# ProDoc_DRV8701_2_2025-04-30.net
KiCad netlist of a schematic drawn in EasyEDA Pro
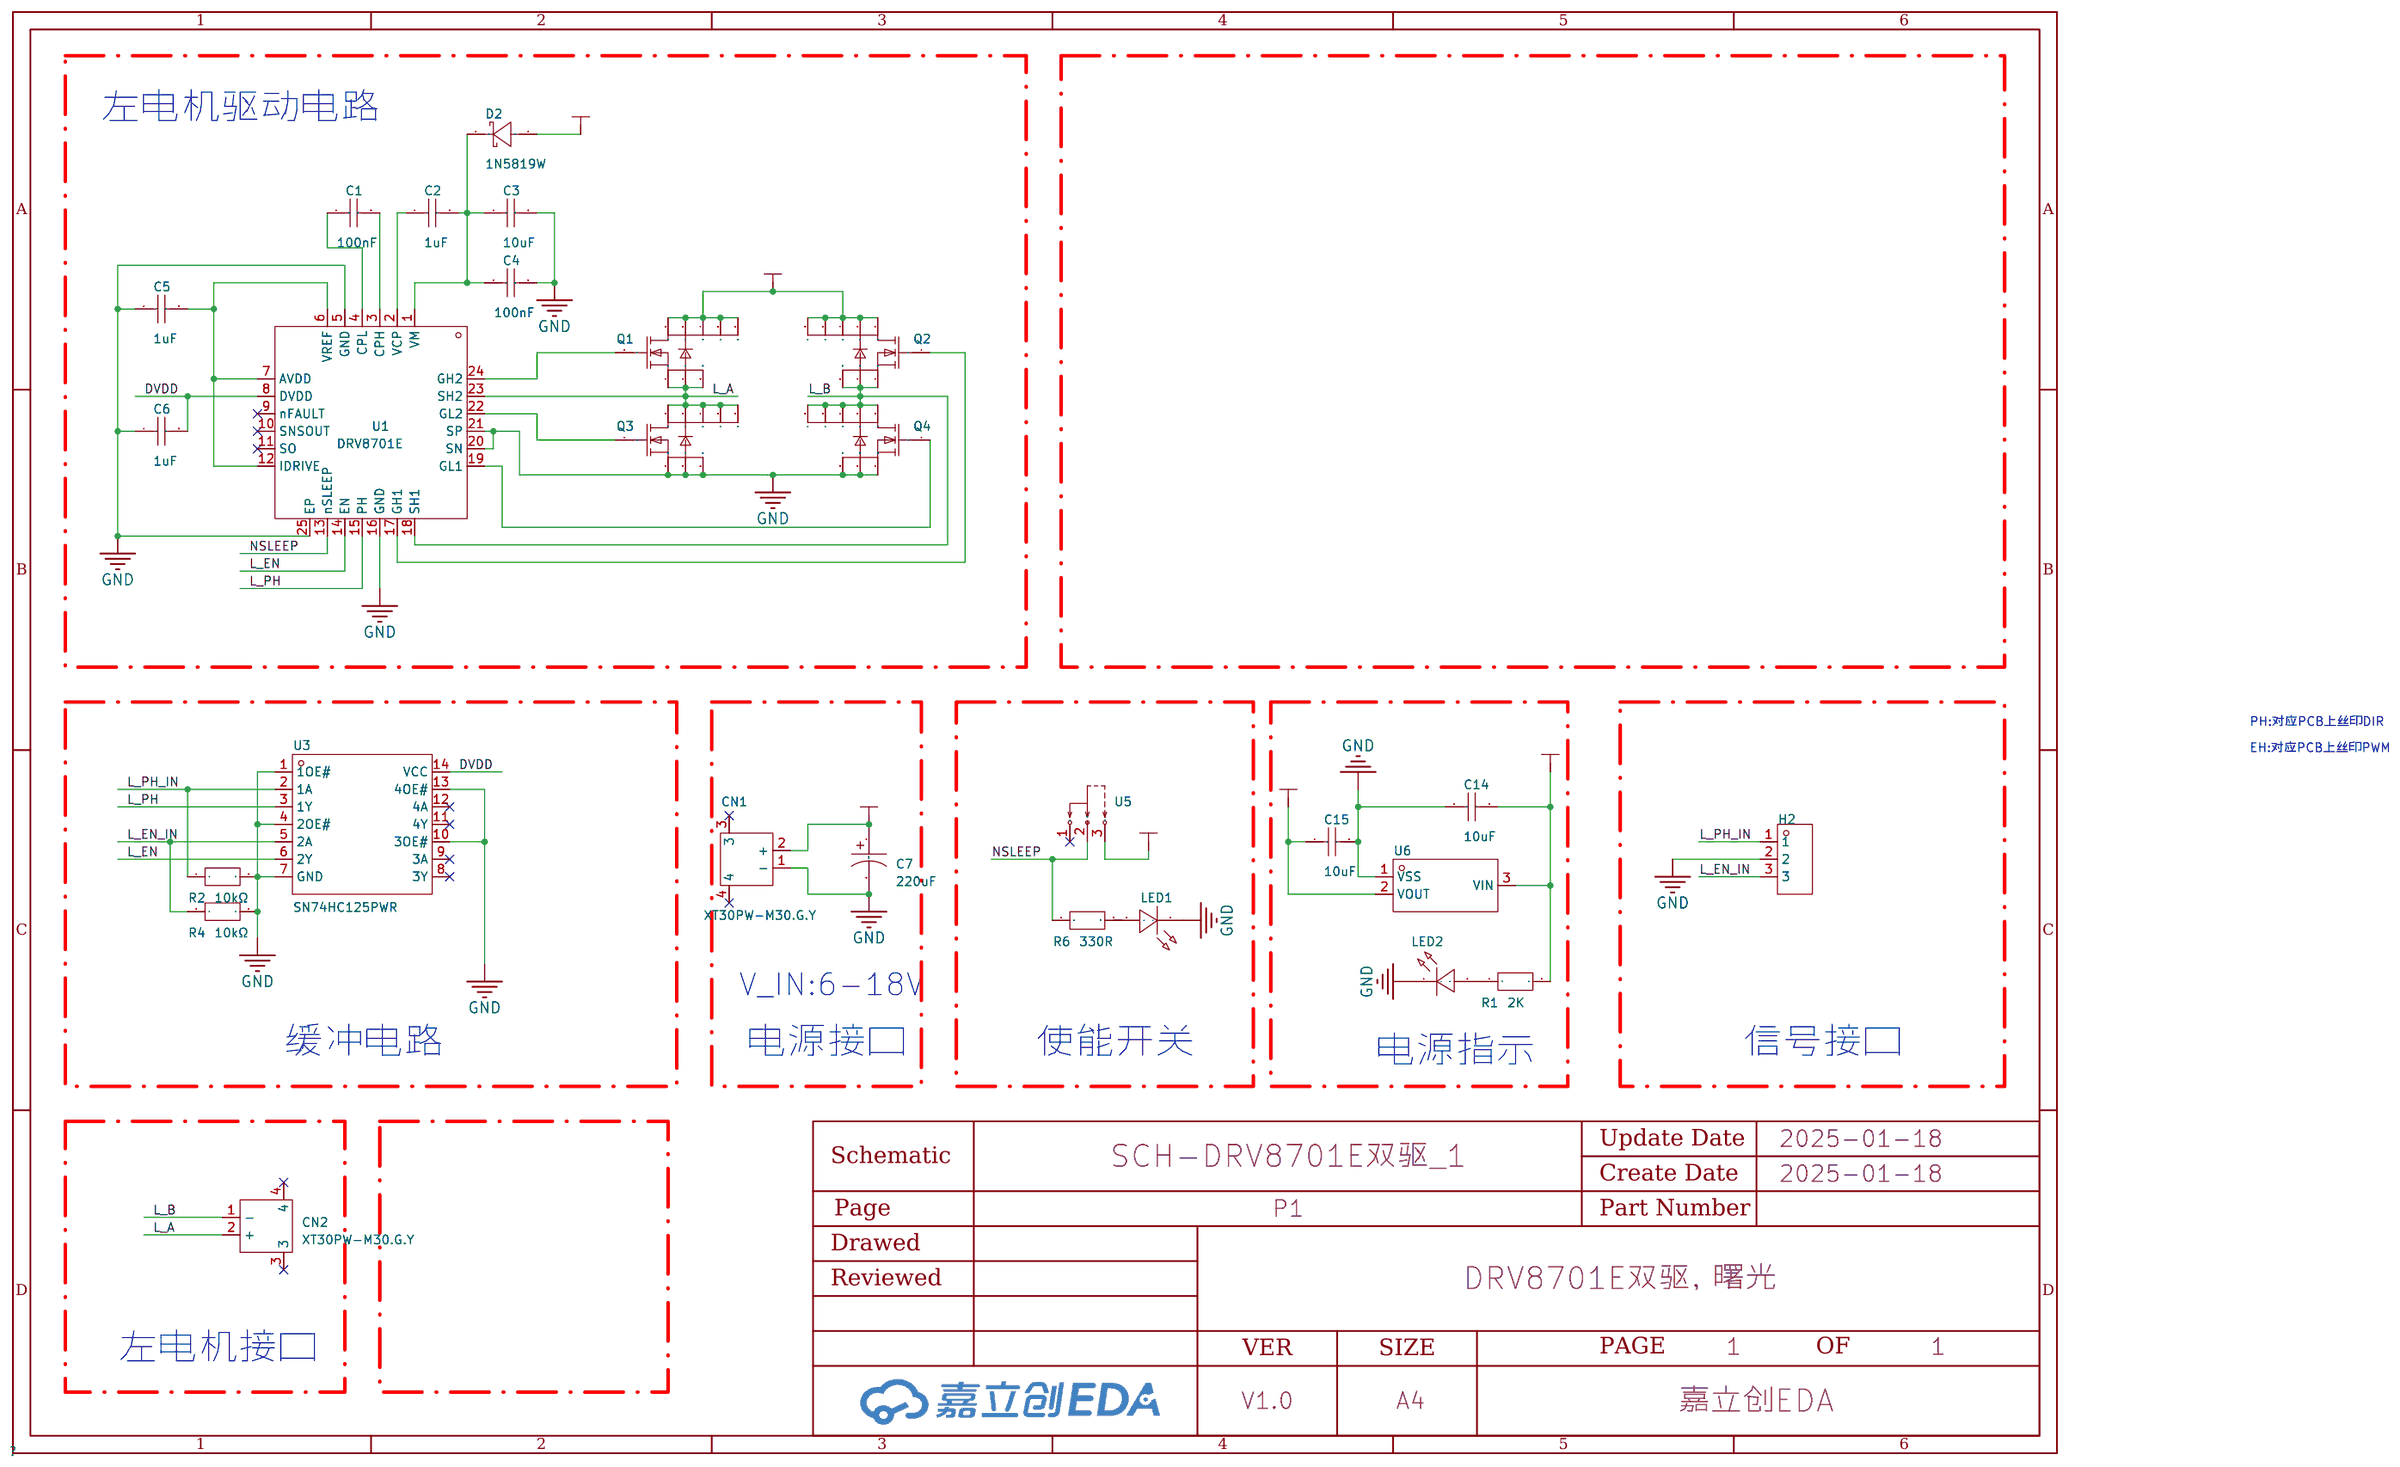
[diagram p0: schematic sheet]

(export (version "E")
  (design (tool "Eeschema 10.0.6"))
  (components
    (comp (ref "C1")
      (value "100nF")
      (footprint "easyedapro:C0805")
      (description "容值:100nF;精度:±10%;额定电压:50V;材质(温度系数):X7R;")
      (fields
        (field (name "Manufacturer Part") "CL21B104KBCNNNC")
        (field (name "Manufacturer") "SAMSUNG(三星)")
      )
      (libsource (lib "easyedapro") (part "CL21B104KBCNNNC"))
    )
    (comp (ref "C2")
      (value "1uF")
      (footprint "easyedapro:C0805")
      (description "容值:100nF;精度:±10%;额定电压:50V;材质(温度系数):X7R;")
      (fields
        (field (name "Manufacturer Part") "CL21B104KBCNNNC")
        (field (name "Manufacturer") "SAMSUNG(三星)")
      )
      (libsource (lib "easyedapro") (part "CL21B104KBCNNNC"))
    )
    (comp (ref "C3")
      (value "10uF")
      (footprint "easyedapro:C0805")
      (description "容值:100nF;精度:±10%;额定电压:50V;材质(温度系数):X7R;")
      (fields
        (field (name "Manufacturer Part") "CL21B104KBCNNNC")
        (field (name "Manufacturer") "SAMSUNG(三星)")
      )
      (libsource (lib "easyedapro") (part "CL21B104KBCNNNC"))
    )
    (comp (ref "C4")
      (value "100nF")
      (footprint "easyedapro:C0805")
      (description "容值:100nF;精度:±10%;额定电压:50V;材质(温度系数):X7R;")
      (fields
        (field (name "Manufacturer Part") "CL21B104KBCNNNC")
        (field (name "Manufacturer") "SAMSUNG(三星)")
      )
      (libsource (lib "easyedapro") (part "CL21B104KBCNNNC"))
    )
    (comp (ref "C5")
      (value "1uF")
      (footprint "easyedapro:C0805")
      (description "容值:100nF;精度:±10%;额定电压:50V;材质(温度系数):X7R;")
      (fields
        (field (name "Manufacturer Part") "CL21B104KBCNNNC")
        (field (name "Manufacturer") "SAMSUNG(三星)")
      )
      (libsource (lib "easyedapro") (part "CL21B104KBCNNNC"))
    )
    (comp (ref "C6")
      (value "1uF")
      (footprint "easyedapro:C0805")
      (description "容值:100nF;精度:±10%;额定电压:50V;材质(温度系数):X7R;")
      (fields
        (field (name "Manufacturer Part") "CL21B104KBCNNNC")
        (field (name "Manufacturer") "SAMSUNG(三星)")
      )
      (libsource (lib "easyedapro") (part "CL21B104KBCNNNC"))
    )
    (comp (ref "C7")
      (value "220uF")
      (footprint "easyedapro:CAP-TH_BD8.0-P3.50-D0.6-FD")
      (fields (field (name "Manufacturer Part") "25PZE220M8X9") (field (name "Manufacturer") "rubycon(红宝石)"))
      (libsource (lib "easyedapro") (part "25PZE220M8X9"))
    )
    (comp (ref "C14")
      (value "10uF")
      (footprint "easyedapro:C0805")
      (description "容值:100nF;精度:±10%;额定电压:50V;材质(温度系数):X7R;")
      (fields
        (field (name "Manufacturer Part") "CL21B104KBCNNNC")
        (field (name "Manufacturer") "SAMSUNG(三星)")
      )
      (libsource (lib "easyedapro") (part "CL21B104KBCNNNC"))
    )
    (comp (ref "C15")
      (value "10uF")
      (footprint "easyedapro:C0805")
      (description "容值:100nF;精度:±10%;额定电压:50V;材质(温度系数):X7R;")
      (fields
        (field (name "Manufacturer Part") "CL21B104KBCNNNC")
        (field (name "Manufacturer") "SAMSUNG(三星)")
      )
      (libsource (lib "easyedapro") (part "CL21B104KBCNNNC"))
    )
    (comp (ref "CN1")
      (value "XT30PW-M30.G.Y")
      (footprint "easyedapro:CONN-TH_XT30PW-M")
      (description "类别:-;类型1:-;")
      (fields (field (name "Manufacturer") "AMASS(艾迈斯)"))
      (libsource (lib "easyedapro") (part "XT30PW-M"))
    )
    (comp (ref "CN2")
      (value "XT30PW-M30.G.Y")
      (footprint "easyedapro:CONN-TH_XT30PW-M")
      (description "类别:-;类型1:-;")
      (fields (field (name "Manufacturer") "AMASS(艾迈斯)"))
      (libsource (lib "easyedapro") (part "XT30PW-M"))
    )
    (comp (ref "D2")
      (value "1N5819W")
      (footprint "easyedapro:SOD-123_L2.7-W1.6-LS3.7-R-RD")
      (description "二极管配置:独立式;直流反向耐压(Vr):40V;平均整流电流(Io):350mA;正向压降(Vf):600mV@200mA;反向电流(Ir):5uA@30V;")
      (fields (field (name "Manufacturer") "JSMSEMI(杰盛微)"))
      (libsource (lib "easyedapro") (part "1N5819W_C963381"))
    )
    (comp (ref "H2")
      (value "~")
      (footprint "easyedapro:HDR-TH_3P-P2.54-V-F")
      (libsource (lib "easyedapro") (part "PM254V-11-03-H85"))
    )
    (comp (ref "LED1")
      (value "P2-0805UVTCS2-0.8T")
      (footprint "easyedapro:LED0805-RD_PURPLE")
      (description "峰值波长:410nm~420nm;发光角度:120°;正向电压:3V;正向电流:30mA;功耗:90mW;工作温度:-40°C~+85°C;抗静电能力:2kV;辐射功率:-;")
      (fields (field (name "Manufacturer") "TUOZHAN(拓展光电)"))
      (libsource (lib "easyedapro") (part "P2-0805UVTCS2-0.8T"))
    )
    (comp (ref "LED2")
      (value "P2-0805UVTCS2-0.8T")
      (footprint "easyedapro:LED0805-RD_PURPLE")
      (description "峰值波长:410nm~420nm;发光角度:120°;正向电压:3V;正向电流:30mA;功耗:90mW;工作温度:-40°C~+85°C;抗静电能力:2kV;辐射功率:-;")
      (fields (field (name "Manufacturer") "TUOZHAN(拓展光电)"))
      (libsource (lib "easyedapro") (part "P2-0805UVTCS2-0.8T"))
    )
    (comp (ref "Q1")
      (value "TPH1R403NL,L1Q(M")
      (footprint "easyedapro:DSOP-8_L5.0-W5.0-P1.27-LS6.0-BL-EP")
      (fields (field (name "Manufacturer") "TOSHIBA(东芝)"))
      (libsource (lib "easyedapro") (part "TPH1R403NL,L1Q(M"))
    )
    (comp (ref "Q2")
      (value "TPH1R403NL,L1Q(M")
      (footprint "easyedapro:DSOP-8_L5.0-W5.0-P1.27-LS6.0-BL-EP")
      (fields (field (name "Manufacturer") "TOSHIBA(东芝)"))
      (libsource (lib "easyedapro") (part "TPH1R403NL,L1Q(M"))
    )
    (comp (ref "Q3")
      (value "TPH1R403NL,L1Q(M")
      (footprint "easyedapro:DSOP-8_L5.0-W5.0-P1.27-LS6.0-BL-EP")
      (fields (field (name "Manufacturer") "TOSHIBA(东芝)"))
      (libsource (lib "easyedapro") (part "TPH1R403NL,L1Q(M"))
    )
    (comp (ref "Q4")
      (value "TPH1R403NL,L1Q(M")
      (footprint "easyedapro:DSOP-8_L5.0-W5.0-P1.27-LS6.0-BL-EP")
      (fields (field (name "Manufacturer") "TOSHIBA(东芝)"))
      (libsource (lib "easyedapro") (part "TPH1R403NL,L1Q(M"))
    )
    (comp (ref "R1")
      (value "2K")
      (footprint "easyedapro:R0805")
      (description "阻值:10kΩ;精度:±5%;功率:500mW;温度系数:±200ppm/°C;最大工作电压:600V;工作温度范围:-55°C~+155°C;")
      (fields (field (name "Manufacturer Part") "ERJP06J103V") (field (name "Manufacturer") "PANASONIC(松下)"))
      (libsource (lib "easyedapro") (part "ERJP06J103V"))
    )
    (comp (ref "R2")
      (value "10kΩ")
      (footprint "easyedapro:R0805")
      (description "阻值:10kΩ;精度:±5%;功率:500mW;温度系数:±200ppm/°C;最大工作电压:600V;工作温度范围:-55°C~+155°C;")
      (fields (field (name "Manufacturer Part") "ERJP06J103V") (field (name "Manufacturer") "PANASONIC(松下)"))
      (libsource (lib "easyedapro") (part "ERJP06J103V"))
    )
    (comp (ref "R4")
      (value "10kΩ")
      (footprint "easyedapro:R0805")
      (description "阻值:10kΩ;精度:±5%;功率:500mW;温度系数:±200ppm/°C;最大工作电压:600V;工作温度范围:-55°C~+155°C;")
      (fields (field (name "Manufacturer Part") "ERJP06J103V") (field (name "Manufacturer") "PANASONIC(松下)"))
      (libsource (lib "easyedapro") (part "ERJP06J103V"))
    )
    (comp (ref "R6")
      (value "330R")
      (footprint "easyedapro:R0805")
      (description "阻值:10kΩ;精度:±5%;功率:500mW;温度系数:±200ppm/°C;最大工作电压:600V;工作温度范围:-55°C~+155°C;")
      (fields (field (name "Manufacturer Part") "ERJP06J103V") (field (name "Manufacturer") "PANASONIC(松下)"))
      (libsource (lib "easyedapro") (part "ERJP06J103V"))
    )
    (comp (ref "U1")
      (value "DRV8701E")
      (footprint "easyedapro:VQFN-24_L4.0-W4.0-P0.50-BL-EP2.5")
      (description "电源电压:0V~5.5V;输出电流:-;接口:并行;")
      (fields (field (name "Manufacturer") "TI(德州仪器)"))
      (libsource (lib "easyedapro") (part "DRV8701ERGET"))
    )
    (comp (ref "U3")
      (value "SN74HC125PWR")
      (footprint "easyedapro:TSSOP-14_L5.0-W4.4-P0.65-LS6.5-BL")
      (description "类型:缓冲器，非反相;电源电压:2V~6V;输入类型:-;输出类型:三态;低电平输出电流(IOL):7.8mA;高电平输出电流(IOH):7.8mA;工作温度:-40°C~+85°C;")
      (fields (field (name "Manufacturer") "TI(德州仪器)"))
      (libsource (lib "easyedapro") (part "SN74HC125PWR"))
    )
    (comp (ref "U5")
      (value "HX SS12D10G4")
      (footprint "easyedapro:SW-TH_SHOU-HAN_SS12D10G4")
      (fields (field (name "Manufacturer") "hanxia(韩下)"))
      (libsource (lib "easyedapro") (part "HX SS12D10G4"))
    )
    (comp (ref "U6")
      (value "LR8341A-T33")
      (footprint "easyedapro:SOT-23-3L_L2.9-W1.6-P1.90-LS2.8-BL")
      (fields (field (name "Manufacturer") "LR(朗瑞)"))
      (libsource (lib "easyedapro") (part "LR8341A-T33"))
    )
  )
  (nets
    (net (code "1") (name "/DVDD") (class "Default")
      (node (ref "C6") (pin "2") (pinfunction "2_2") (pintype "input"))
      (node (ref "U1") (pin "8") (pinfunction "DVDD_8") (pintype "input"))
      (node (ref "U3") (pin "14") (pinfunction "VCC_14") (pintype "input"))
    )
    (net (code "2") (name "/L_A") (class "Default")
      (node (ref "CN2") (pin "2") (pinfunction "+_2") (pintype "unspecified"))
      (node (ref "Q1") (pin "1") (pinfunction "S_1") (pintype "input"))
      (node (ref "Q1") (pin "2") (pinfunction "S_2") (pintype "input"))
      (node (ref "Q1") (pin "3") (pinfunction "S_3") (pintype "input"))
      (node (ref "Q3") (pin "5") (pinfunction "D_5") (pintype "input"))
      (node (ref "Q3") (pin "6") (pinfunction "D_6") (pintype "input"))
      (node (ref "Q3") (pin "7") (pinfunction "D_7") (pintype "input"))
      (node (ref "Q3") (pin "8") (pinfunction "D_8") (pintype "input"))
      (node (ref "Q3") (pin "9") (pinfunction "D_9") (pintype "input"))
      (node (ref "U1") (pin "23") (pinfunction "SH2_23") (pintype "input"))
    )
    (net (code "3") (name "/L_B") (class "Default")
      (node (ref "CN2") (pin "1") (pinfunction "-_1") (pintype "unspecified"))
      (node (ref "Q2") (pin "1") (pinfunction "S_1") (pintype "input"))
      (node (ref "Q2") (pin "2") (pinfunction "S_2") (pintype "input"))
      (node (ref "Q2") (pin "3") (pinfunction "S_3") (pintype "input"))
      (node (ref "Q4") (pin "5") (pinfunction "D_5") (pintype "input"))
      (node (ref "Q4") (pin "6") (pinfunction "D_6") (pintype "input"))
      (node (ref "Q4") (pin "7") (pinfunction "D_7") (pintype "input"))
      (node (ref "Q4") (pin "8") (pinfunction "D_8") (pintype "input"))
      (node (ref "Q4") (pin "9") (pinfunction "D_9") (pintype "input"))
      (node (ref "U1") (pin "18") (pinfunction "SH1_18") (pintype "input"))
    )
    (net (code "4") (name "/L_EN") (class "Default")
      (node (ref "U1") (pin "14") (pinfunction "EN_14") (pintype "input"))
      (node (ref "U3") (pin "6") (pinfunction "2Y_6") (pintype "input"))
    )
    (net (code "5") (name "/L_EN_IN") (class "Default")
      (node (ref "H2") (pin "3") (pinfunction "3_3") (pintype "unspecified"))
      (node (ref "R4") (pin "1") (pinfunction "1_1") (pintype "input"))
      (node (ref "U3") (pin "5") (pinfunction "2A_5") (pintype "input"))
    )
    (net (code "6") (name "/L_PH") (class "Default")
      (node (ref "U1") (pin "15") (pinfunction "PH_15") (pintype "input"))
      (node (ref "U3") (pin "3") (pinfunction "1Y_3") (pintype "input"))
    )
    (net (code "7") (name "/L_PH_IN") (class "Default")
      (node (ref "H2") (pin "1") (pinfunction "1_1") (pintype "unspecified"))
      (node (ref "R2") (pin "1") (pinfunction "1_1") (pintype "input"))
      (node (ref "U3") (pin "2") (pinfunction "1A_2") (pintype "input"))
    )
    (net (code "8") (name "/NSLEEP") (class "Default")
      (node (ref "R6") (pin "1") (pinfunction "1_1") (pintype "input"))
      (node (ref "U1") (pin "13") (pinfunction "nSLEEP_13") (pintype "input"))
      (node (ref "U5") (pin "2") (pinfunction "2_2") (pintype "input"))
    )
    (net (code "9") (name "3V3") (class "Default")
      (node (ref "C15") (pin "1") (pinfunction "1_1") (pintype "input"))
      (node (ref "U5") (pin "3") (pinfunction "3_3") (pintype "input"))
      (node (ref "U6") (pin "2") (pinfunction "VOUT_2") (pintype "input"))
    )
    (net (code "10") (name "GND") (class "Default")
      (node (ref "C14") (pin "1") (pinfunction "1_1") (pintype "input"))
      (node (ref "C15") (pin "2") (pinfunction "2_2") (pintype "input"))
      (node (ref "C3") (pin "2") (pinfunction "2_2") (pintype "input"))
      (node (ref "C4") (pin "2") (pinfunction "2_2") (pintype "input"))
      (node (ref "C5") (pin "1") (pinfunction "1_1") (pintype "input"))
      (node (ref "C6") (pin "1") (pinfunction "1_1") (pintype "input"))
      (node (ref "C7") (pin "2") (pinfunction "2_2") (pintype "input"))
      (node (ref "CN1") (pin "1") (pinfunction "-_1") (pintype "unspecified"))
      (node (ref "H2") (pin "2") (pinfunction "2_2") (pintype "unspecified"))
      (node (ref "LED1") (pin "1") (pinfunction "-_1") (pintype "input"))
      (node (ref "LED2") (pin "1") (pinfunction "-_1") (pintype "input"))
      (node (ref "Q3") (pin "1") (pinfunction "S_1") (pintype "input"))
      (node (ref "Q3") (pin "2") (pinfunction "S_2") (pintype "input"))
      (node (ref "Q3") (pin "3") (pinfunction "S_3") (pintype "input"))
      (node (ref "Q4") (pin "1") (pinfunction "S_1") (pintype "input"))
      (node (ref "Q4") (pin "2") (pinfunction "S_2") (pintype "input"))
      (node (ref "Q4") (pin "3") (pinfunction "S_3") (pintype "input"))
      (node (ref "R2") (pin "2") (pinfunction "2_2") (pintype "input"))
      (node (ref "R4") (pin "2") (pinfunction "2_2") (pintype "input"))
      (node (ref "U1") (pin "16") (pinfunction "GND_16") (pintype "input"))
      (node (ref "U1") (pin "20") (pinfunction "SN_20") (pintype "input"))
      (node (ref "U1") (pin "21") (pinfunction "SP_21") (pintype "input"))
      (node (ref "U1") (pin "25") (pinfunction "EP_25") (pintype "input"))
      (node (ref "U1") (pin "5") (pinfunction "GND_5") (pintype "input"))
      (node (ref "U3") (pin "1") (pinfunction "1OE#_1") (pintype "input"))
      (node (ref "U3") (pin "10") (pinfunction "3OE#_10") (pintype "input"))
      (node (ref "U3") (pin "13") (pinfunction "4OE#_13") (pintype "input"))
      (node (ref "U3") (pin "4") (pinfunction "2OE#_4") (pintype "input"))
      (node (ref "U3") (pin "7") (pinfunction "GND_7") (pintype "input"))
      (node (ref "U6") (pin "1") (pinfunction "VSS_1") (pintype "input"))
    )
    (net (code "11") (name "Net-(D2-C)") (class "Default")
      (node (ref "C2") (pin "2") (pinfunction "2_2") (pintype "input"))
      (node (ref "C3") (pin "1") (pinfunction "1_1") (pintype "input"))
      (node (ref "C4") (pin "1") (pinfunction "1_1") (pintype "input"))
      (node (ref "D2") (pin "2") (pinfunction "C_2") (pintype "input"))
      (node (ref "U1") (pin "1") (pinfunction "VM_1") (pintype "input"))
    )
    (net (code "12") (name "Net-(LED1-+)") (class "Default")
      (node (ref "LED1") (pin "2") (pinfunction "+_2") (pintype "input"))
      (node (ref "R6") (pin "2") (pinfunction "2_2") (pintype "input"))
    )
    (net (code "13") (name "Net-(LED2-+)") (class "Default")
      (node (ref "LED2") (pin "2") (pinfunction "+_2") (pintype "input"))
      (node (ref "R1") (pin "1") (pinfunction "1_1") (pintype "input"))
    )
    (net (code "14") (name "Net-(Q1-G)") (class "Default")
      (node (ref "Q1") (pin "4") (pinfunction "G_4") (pintype "input"))
      (node (ref "U1") (pin "24") (pinfunction "GH2_24") (pintype "input"))
    )
    (net (code "15") (name "Net-(Q2-G)") (class "Default")
      (node (ref "Q2") (pin "4") (pinfunction "G_4") (pintype "input"))
      (node (ref "U1") (pin "17") (pinfunction "GH1_17") (pintype "input"))
    )
    (net (code "16") (name "Net-(Q3-G)") (class "Default")
      (node (ref "Q3") (pin "4") (pinfunction "G_4") (pintype "input"))
      (node (ref "U1") (pin "22") (pinfunction "GL2_22") (pintype "input"))
    )
    (net (code "17") (name "Net-(Q4-G)") (class "Default")
      (node (ref "Q4") (pin "4") (pinfunction "G_4") (pintype "input"))
      (node (ref "U1") (pin "19") (pinfunction "GL1_19") (pintype "input"))
    )
    (net (code "18") (name "Net-(U1-AVDD)") (class "Default")
      (node (ref "C5") (pin "2") (pinfunction "2_2") (pintype "input"))
      (node (ref "U1") (pin "12") (pinfunction "IDRIVE_12") (pintype "input"))
      (node (ref "U1") (pin "6") (pinfunction "VREF_6") (pintype "input"))
      (node (ref "U1") (pin "7") (pinfunction "AVDD_7") (pintype "input"))
    )
    (net (code "19") (name "Net-(U1-CPH)") (class "Default")
      (node (ref "C1") (pin "2") (pinfunction "2_2") (pintype "input"))
      (node (ref "U1") (pin "3") (pinfunction "CPH_3") (pintype "input"))
    )
    (net (code "20") (name "Net-(U1-CPL)") (class "Default")
      (node (ref "C1") (pin "1") (pinfunction "1_1") (pintype "input"))
      (node (ref "U1") (pin "4") (pinfunction "CPL_4") (pintype "input"))
    )
    (net (code "21") (name "Net-(U1-VCP)") (class "Default")
      (node (ref "C2") (pin "1") (pinfunction "1_1") (pintype "input"))
      (node (ref "U1") (pin "2") (pinfunction "VCP_2") (pintype "input"))
    )
    (net (code "22") (name "VM") (class "Default")
      (node (ref "C14") (pin "2") (pinfunction "2_2") (pintype "input"))
      (node (ref "C7") (pin "1") (pinfunction "1_1") (pintype "input"))
      (node (ref "CN1") (pin "2") (pinfunction "+_2") (pintype "unspecified"))
      (node (ref "D2") (pin "1") (pinfunction "A_1") (pintype "input"))
      (node (ref "Q1") (pin "5") (pinfunction "D_5") (pintype "input"))
      (node (ref "Q1") (pin "6") (pinfunction "D_6") (pintype "input"))
      (node (ref "Q1") (pin "7") (pinfunction "D_7") (pintype "input"))
      (node (ref "Q1") (pin "8") (pinfunction "D_8") (pintype "input"))
      (node (ref "Q1") (pin "9") (pinfunction "D_9") (pintype "input"))
      (node (ref "Q2") (pin "5") (pinfunction "D_5") (pintype "input"))
      (node (ref "Q2") (pin "6") (pinfunction "D_6") (pintype "input"))
      (node (ref "Q2") (pin "7") (pinfunction "D_7") (pintype "input"))
      (node (ref "Q2") (pin "8") (pinfunction "D_8") (pintype "input"))
      (node (ref "Q2") (pin "9") (pinfunction "D_9") (pintype "input"))
      (node (ref "R1") (pin "2") (pinfunction "2_2") (pintype "input"))
      (node (ref "U6") (pin "3") (pinfunction "VIN_3") (pintype "input"))
    )
    (net (code "23") (name "unconnected-(CN1-Pad3)") (class "Default")
      (node (ref "CN1") (pin "3") (pinfunction "3_3") (pintype "unspecified+no_connect"))
    )
    (net (code "24") (name "unconnected-(CN1-Pad4)") (class "Default")
      (node (ref "CN1") (pin "4") (pinfunction "4_4") (pintype "unspecified+no_connect"))
    )
    (net (code "25") (name "unconnected-(CN2-Pad3)") (class "Default")
      (node (ref "CN2") (pin "3") (pinfunction "3_3") (pintype "unspecified+no_connect"))
    )
    (net (code "26") (name "unconnected-(CN2-Pad4)") (class "Default")
      (node (ref "CN2") (pin "4") (pinfunction "4_4") (pintype "unspecified+no_connect"))
    )
    (net (code "27") (name "unconnected-(U1-SNSOUT-Pad10)") (class "Default")
      (node (ref "U1") (pin "10") (pinfunction "SNSOUT_10") (pintype "input+no_connect"))
    )
    (net (code "28") (name "unconnected-(U1-SO-Pad11)") (class "Default")
      (node (ref "U1") (pin "11") (pinfunction "SO_11") (pintype "input+no_connect"))
    )
    (net (code "29") (name "unconnected-(U1-nFAULT-Pad9)") (class "Default")
      (node (ref "U1") (pin "9") (pinfunction "nFAULT_9") (pintype "input+no_connect"))
    )
    (net (code "30") (name "unconnected-(U3-3A-Pad9)") (class "Default")
      (node (ref "U3") (pin "9") (pinfunction "3A_9") (pintype "input+no_connect"))
    )
    (net (code "31") (name "unconnected-(U3-3Y-Pad8)") (class "Default")
      (node (ref "U3") (pin "8") (pinfunction "3Y_8") (pintype "input+no_connect"))
    )
    (net (code "32") (name "unconnected-(U3-4A-Pad12)") (class "Default")
      (node (ref "U3") (pin "12") (pinfunction "4A_12") (pintype "input+no_connect"))
    )
    (net (code "33") (name "unconnected-(U3-4Y-Pad11)") (class "Default")
      (node (ref "U3") (pin "11") (pinfunction "4Y_11") (pintype "input+no_connect"))
    )
    (net (code "34") (name "unconnected-(U5-Pad1)") (class "Default")
      (node (ref "U5") (pin "1") (pinfunction "1_1") (pintype "input+no_connect"))
    )
  )
)
